# edition4-mainpart-5.net
KiCad netlist of a schematic drawn in EAGLE
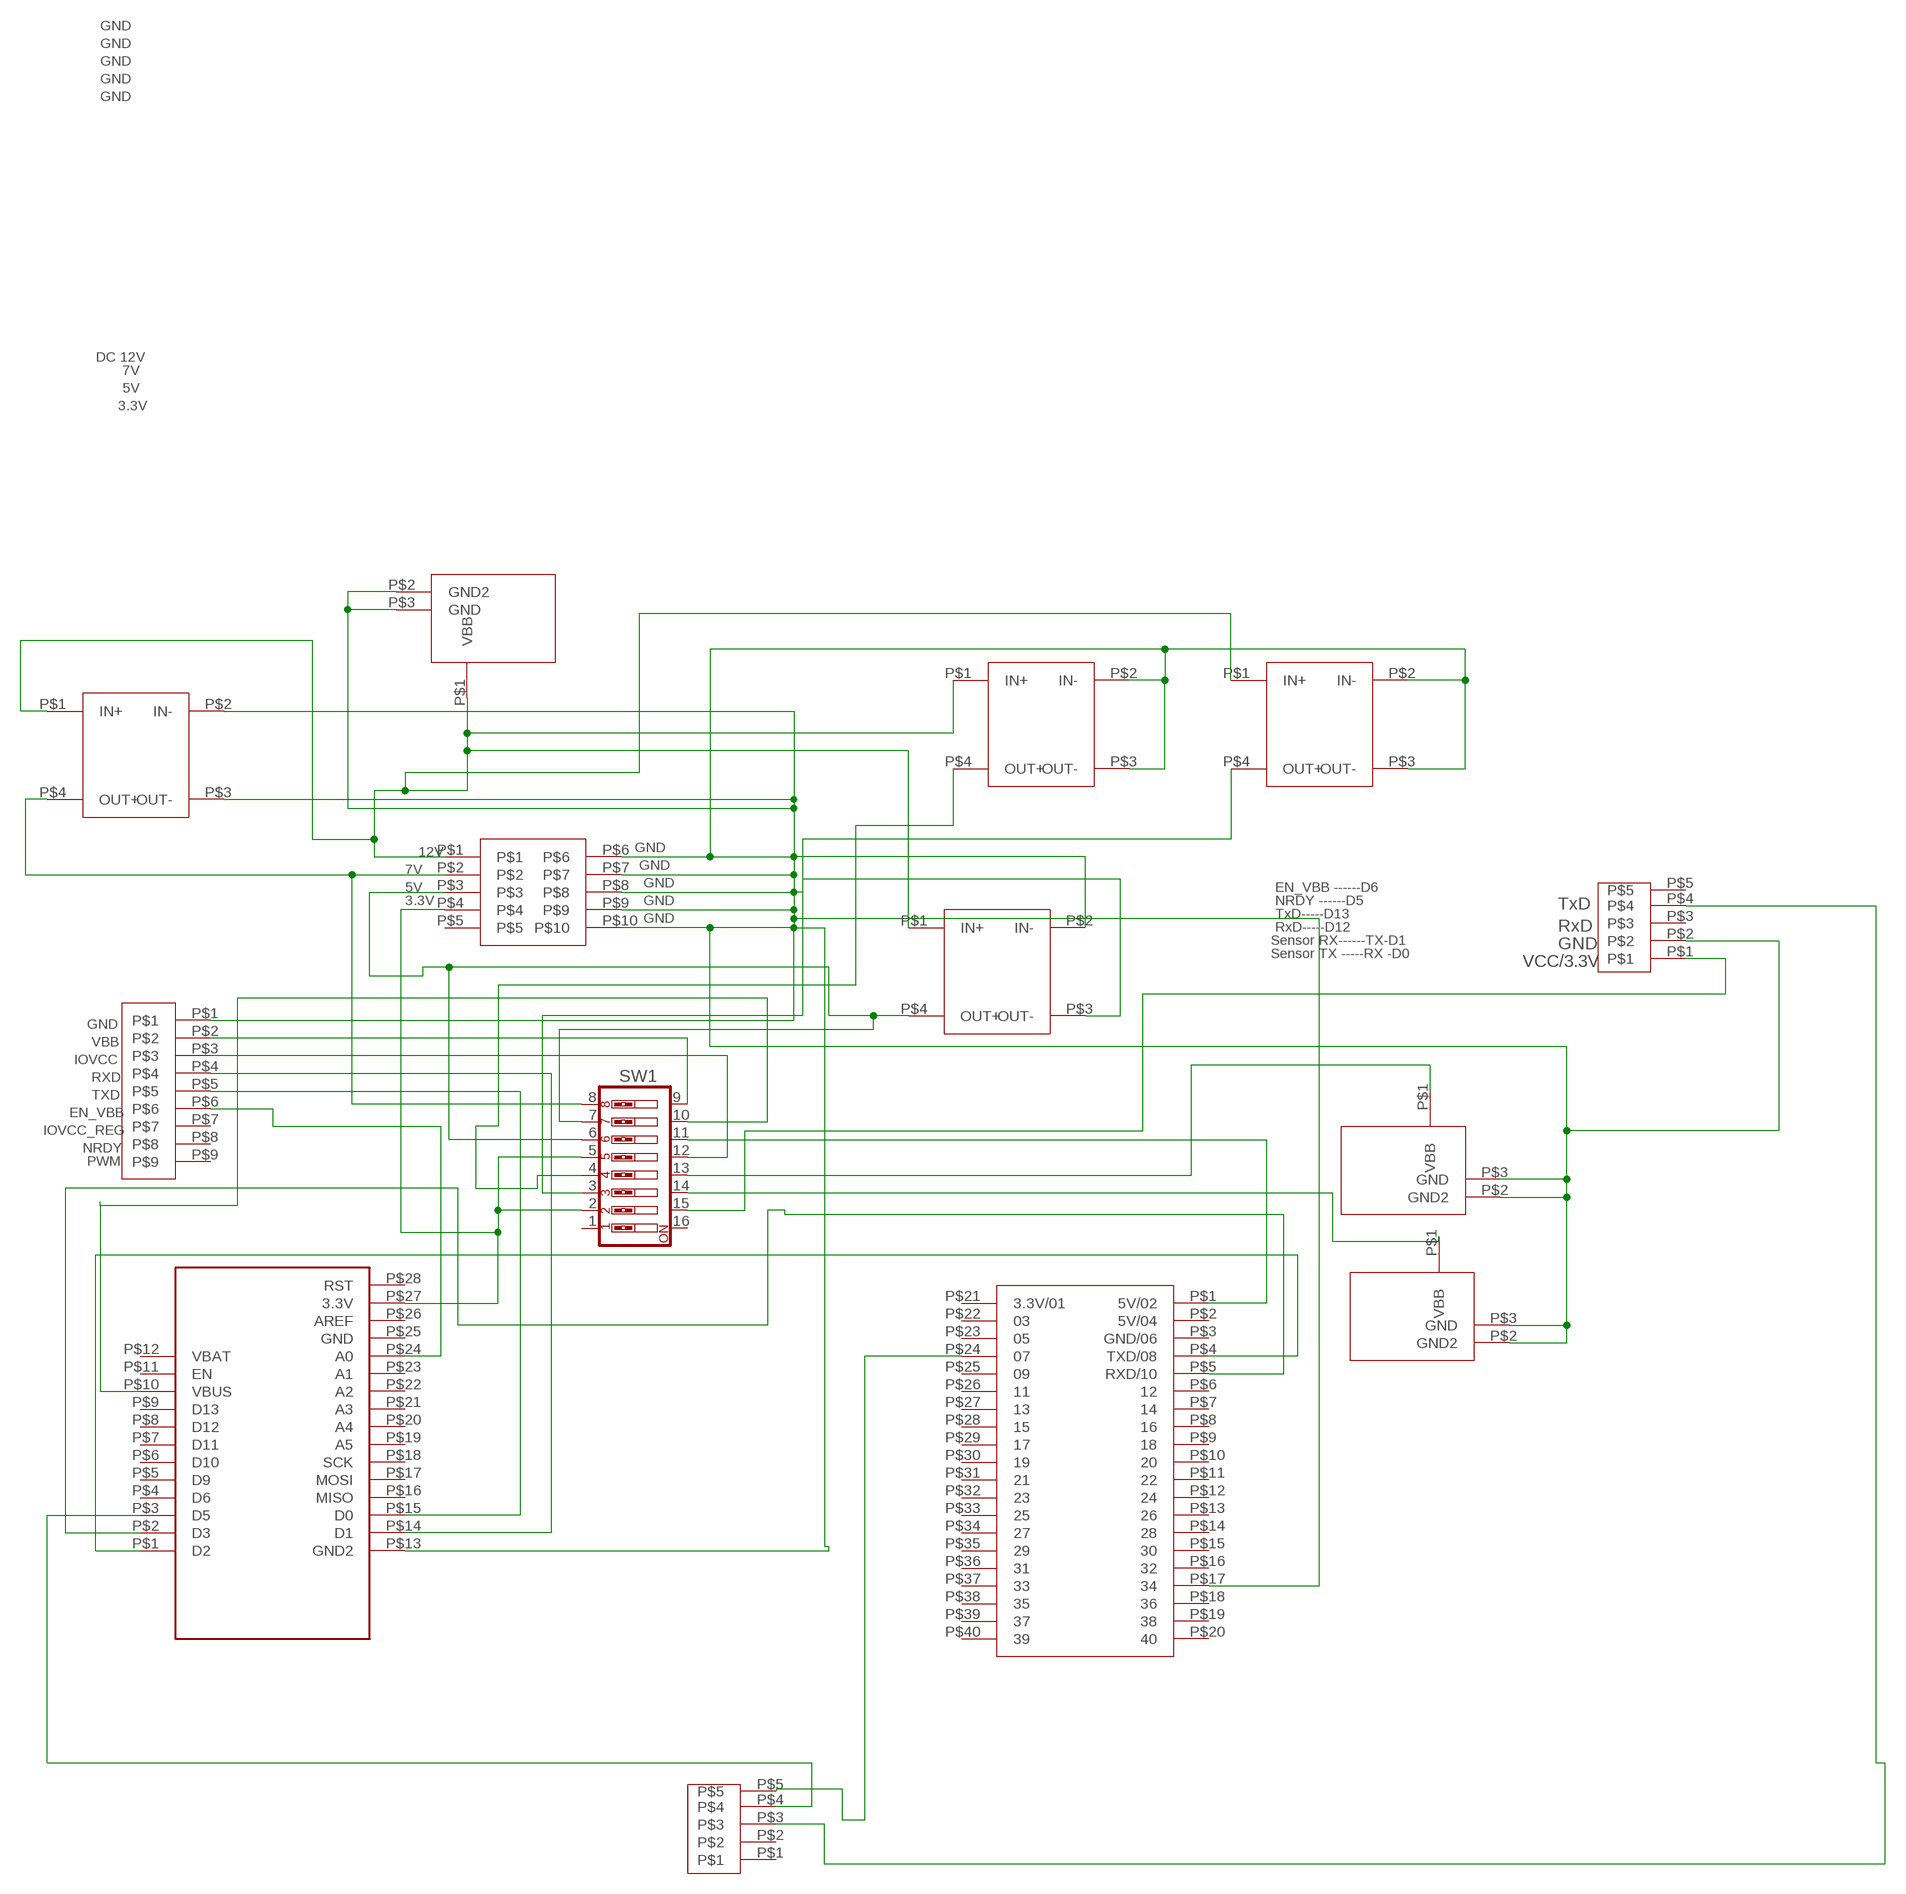
[diagram p0: schematic, sheet 1]

(export (version "E")
  (design (tool "Eeschema 10.0.6"))
  (components
    (comp (ref "SW1")
      (value "SW_DIP-8")
      (footprint "eagle-import:EDG-08")
      (libsource (lib "eagle-import") (part "SW_DIP-8"))
    )
    (comp (ref "U$1")
      (value "MH-MINI-360")
      (footprint "eagle-import:MH-MINI-360")
      (libsource (lib "eagle-import") (part "MH-MINI-360"))
    )
    (comp (ref "U$2")
      (value "MH-MINI-360")
      (footprint "eagle-import:MH-MINI-360")
      (libsource (lib "eagle-import") (part "MH-MINI-360"))
    )
    (comp (ref "U$3")
      (value "POWER")
      (footprint "eagle-import:POWERIN")
      (libsource (lib "eagle-import") (part "POWER"))
    )
    (comp (ref "U$4")
      (value "POWER")
      (footprint "eagle-import:POWERIN")
      (libsource (lib "eagle-import") (part "POWER"))
    )
    (comp (ref "U$5")
      (value "POWER")
      (footprint "eagle-import:POWERIN")
      (libsource (lib "eagle-import") (part "POWER"))
    )
    (comp (ref "U$6")
      (value "MH-MINI-360")
      (footprint "eagle-import:MH-MINI-360")
      (libsource (lib "eagle-import") (part "MH-MINI-360"))
    )
    (comp (ref "U$7")
      (value "MH-MINI-360")
      (footprint "eagle-import:MH-MINI-360")
      (libsource (lib "eagle-import") (part "MH-MINI-360"))
    )
    (comp (ref "U$8")
      (value "PIN")
      (footprint "eagle-import:PIN")
      (libsource (lib "eagle-import") (part "PIN"))
    )
    (comp (ref "U$9")
      (value "PIN")
      (footprint "eagle-import:PIN")
      (libsource (lib "eagle-import") (part "untitled (1)_PIN"))
    )
    (comp (ref "U$10")
      (value "FEATHER")
      (footprint "eagle-import:FEATHER")
      (libsource (lib "eagle-import") (part "FEATHER"))
    )
    (comp (ref "U$11")
      (value "RASPBERRYPI")
      (footprint "eagle-import:RASPBERRYPI")
      (libsource (lib "eagle-import") (part "RASPBERRYPI"))
    )
    (comp (ref "U$14")
      (value "2X5FEET")
      (footprint "eagle-import:2X5FEET")
      (libsource (lib "eagle-import") (part "2X5FEET"))
    )
    (comp (ref "U$15")
      (value "9FEETPIN")
      (footprint "eagle-import:9FEETPIN")
      (libsource (lib "eagle-import") (part "9FEETPIN"))
    )
  )
  (nets
    (net (code "1") (name "Net-(SW1-Pad9)") (class "Default")
      (node (ref "SW1") (pin "9") (pinfunction "9_9") (pintype "passive"))
      (node (ref "U$15") (pin "P$2") (pinfunction "P$2_P$2") (pintype "bidirectional"))
    )
    (net (code "2") (name "Net-(SW1-Pad12)") (class "Default")
      (node (ref "SW1") (pin "12") (pinfunction "12_12") (pintype "passive"))
      (node (ref "U$15") (pin "P$3") (pinfunction "P$3_P$3") (pintype "bidirectional"))
    )
    (net (code "3") (name "Net-(SW1-Pad15)") (class "Default")
      (node (ref "SW1") (pin "15") (pinfunction "15_15") (pintype "passive"))
      (node (ref "U$8") (pin "P$1") (pinfunction "P$1_P$1") (pintype "bidirectional"))
    )
    (net (code "4") (name "Net-(U$1-IN+)") (class "Default")
      (node (ref "U$1") (pin "P$1") (pinfunction "IN+_P$1") (pintype "bidirectional"))
      (node (ref "U$14") (pin "P$1") (pinfunction "P$1_P$1") (pintype "bidirectional"))
      (node (ref "U$2") (pin "P$1") (pinfunction "IN+_P$1") (pintype "bidirectional"))
      (node (ref "U$3") (pin "P$1") (pinfunction "VBB_P$1") (pintype "bidirectional"))
      (node (ref "U$6") (pin "P$1") (pinfunction "IN+_P$1") (pintype "bidirectional"))
      (node (ref "U$7") (pin "P$1") (pinfunction "IN+_P$1") (pintype "bidirectional"))
    )
    (net (code "5") (name "Net-(U$1-IN-)") (class "Default")
      (node (ref "U$1") (pin "P$2") (pinfunction "IN-_P$2") (pintype "bidirectional"))
      (node (ref "U$1") (pin "P$3") (pinfunction "OUT-_P$3") (pintype "bidirectional"))
      (node (ref "U$10") (pin "P$13") (pinfunction "GND2_P$13") (pintype "bidirectional"))
      (node (ref "U$11") (pin "P$17") (pinfunction "34_P$17") (pintype "bidirectional"))
      (node (ref "U$14") (pin "P$10") (pinfunction "P$10_P$10") (pintype "bidirectional"))
      (node (ref "U$14") (pin "P$6") (pinfunction "P$6_P$6") (pintype "bidirectional"))
      (node (ref "U$14") (pin "P$7") (pinfunction "P$7_P$7") (pintype "bidirectional"))
      (node (ref "U$14") (pin "P$8") (pinfunction "P$8_P$8") (pintype "bidirectional"))
      (node (ref "U$14") (pin "P$9") (pinfunction "P$9_P$9") (pintype "bidirectional"))
      (node (ref "U$15") (pin "P$1") (pinfunction "P$1_P$1") (pintype "bidirectional"))
      (node (ref "U$2") (pin "P$2") (pinfunction "IN-_P$2") (pintype "bidirectional"))
      (node (ref "U$2") (pin "P$3") (pinfunction "OUT-_P$3") (pintype "bidirectional"))
      (node (ref "U$3") (pin "P$2") (pinfunction "GND2_P$2") (pintype "bidirectional"))
      (node (ref "U$3") (pin "P$3") (pinfunction "GND_P$3") (pintype "bidirectional"))
      (node (ref "U$4") (pin "P$2") (pinfunction "GND2_P$2") (pintype "bidirectional"))
      (node (ref "U$4") (pin "P$3") (pinfunction "GND_P$3") (pintype "bidirectional"))
      (node (ref "U$5") (pin "P$2") (pinfunction "GND2_P$2") (pintype "bidirectional"))
      (node (ref "U$5") (pin "P$3") (pinfunction "GND_P$3") (pintype "bidirectional"))
      (node (ref "U$6") (pin "P$2") (pinfunction "IN-_P$2") (pintype "bidirectional"))
      (node (ref "U$6") (pin "P$3") (pinfunction "OUT-_P$3") (pintype "bidirectional"))
      (node (ref "U$7") (pin "P$2") (pinfunction "IN-_P$2") (pintype "bidirectional"))
      (node (ref "U$7") (pin "P$3") (pinfunction "OUT-_P$3") (pintype "bidirectional"))
      (node (ref "U$8") (pin "P$2") (pinfunction "P$2_P$2") (pintype "bidirectional"))
    )
    (net (code "6") (name "Net-(U$1-OUT+)") (class "Default")
      (node (ref "SW1") (pin "4") (pinfunction "4_4") (pintype "passive"))
      (node (ref "U$1") (pin "P$4") (pinfunction "OUT+_P$4") (pintype "bidirectional"))
    )
    (net (code "7") (name "Net-(U$2-OUT+)") (class "Default")
      (node (ref "SW1") (pin "6") (pinfunction "6_6") (pintype "passive"))
      (node (ref "SW1") (pin "7") (pinfunction "7_7") (pintype "passive"))
      (node (ref "U$14") (pin "P$3") (pinfunction "P$3_P$3") (pintype "bidirectional"))
      (node (ref "U$2") (pin "P$4") (pinfunction "OUT+_P$4") (pintype "bidirectional"))
    )
    (net (code "8") (name "Net-(U$4-VBB)") (class "Default")
      (node (ref "SW1") (pin "14") (pinfunction "14_14") (pintype "passive"))
      (node (ref "U$4") (pin "P$1") (pinfunction "VBB_P$1") (pintype "bidirectional"))
    )
    (net (code "9") (name "Net-(U$5-VBB)") (class "Default")
      (node (ref "SW1") (pin "13") (pinfunction "13_13") (pintype "passive"))
      (node (ref "U$5") (pin "P$1") (pinfunction "VBB_P$1") (pintype "bidirectional"))
    )
    (net (code "10") (name "Net-(U$6-OUT+)") (class "Default")
      (node (ref "SW1") (pin "8") (pinfunction "8_8") (pintype "passive"))
      (node (ref "U$14") (pin "P$2") (pinfunction "P$2_P$2") (pintype "bidirectional"))
      (node (ref "U$6") (pin "P$4") (pinfunction "OUT+_P$4") (pintype "bidirectional"))
    )
    (net (code "11") (name "Net-(U$7-OUT+)") (class "Default")
      (node (ref "SW1") (pin "3") (pinfunction "3_3") (pintype "passive"))
      (node (ref "U$7") (pin "P$4") (pinfunction "OUT+_P$4") (pintype "bidirectional"))
    )
    (net (code "12") (name "Net-(U$8-PadP$4)") (class "Default")
      (node (ref "U$8") (pin "P$4") (pinfunction "P$4_P$4") (pintype "bidirectional"))
      (node (ref "U$9") (pin "P$3") (pinfunction "P$3_P$3") (pintype "bidirectional"))
    )
    (net (code "13") (name "Net-(U$10-3.3V)") (class "Default")
      (node (ref "SW1") (pin "2") (pinfunction "2_2") (pintype "passive"))
      (node (ref "SW1") (pin "5") (pinfunction "5_5") (pintype "passive"))
      (node (ref "U$10") (pin "P$27") (pinfunction "3.3V_P$27") (pintype "bidirectional"))
      (node (ref "U$14") (pin "P$4") (pinfunction "P$4_P$4") (pintype "bidirectional"))
    )
    (net (code "14") (name "Net-(U$10-A0)") (class "Default")
      (node (ref "U$10") (pin "P$24") (pinfunction "A0_P$24") (pintype "bidirectional"))
      (node (ref "U$15") (pin "P$6") (pinfunction "P$6_P$6") (pintype "bidirectional"))
    )
    (net (code "15") (name "Net-(U$10-D0)") (class "Default")
      (node (ref "U$10") (pin "P$15") (pinfunction "D0_P$15") (pintype "bidirectional"))
      (node (ref "U$15") (pin "P$5") (pinfunction "P$5_P$5") (pintype "bidirectional"))
    )
    (net (code "16") (name "Net-(U$10-D1)") (class "Default")
      (node (ref "U$10") (pin "P$14") (pinfunction "D1_P$14") (pintype "bidirectional"))
      (node (ref "U$15") (pin "P$4") (pinfunction "P$4_P$4") (pintype "bidirectional"))
    )
    (net (code "17") (name "Net-(U$10-D2)") (class "Default")
      (node (ref "U$10") (pin "P$1") (pinfunction "D2_P$1") (pintype "bidirectional"))
      (node (ref "U$11") (pin "P$4") (pinfunction "TXD/08_P$4") (pintype "bidirectional"))
    )
    (net (code "18") (name "Net-(U$10-D3)") (class "Default")
      (node (ref "U$10") (pin "P$2") (pinfunction "D3_P$2") (pintype "bidirectional"))
      (node (ref "U$11") (pin "P$5") (pinfunction "RXD/10_P$5") (pintype "bidirectional"))
    )
    (net (code "19") (name "Net-(U$10-D5)") (class "Default")
      (node (ref "U$10") (pin "P$3") (pinfunction "D5_P$3") (pintype "bidirectional"))
      (node (ref "U$9") (pin "P$4") (pinfunction "P$4_P$4") (pintype "bidirectional"))
    )
    (net (code "20") (name "Net-(U$10-VBUS)") (class "Default")
      (node (ref "SW1") (pin "10") (pinfunction "10_10") (pintype "passive"))
      (node (ref "U$10") (pin "P$10") (pinfunction "VBUS_P$10") (pintype "bidirectional"))
    )
    (net (code "21") (name "Net-(U$11-5V{slash}02)") (class "Default")
      (node (ref "SW1") (pin "11") (pinfunction "11_11") (pintype "passive"))
      (node (ref "U$11") (pin "P$1") (pinfunction "5V/02_P$1") (pintype "bidirectional"))
    )
    (net (code "22") (name "Net-(U$11-07)") (class "Default")
      (node (ref "U$11") (pin "P$24") (pinfunction "07_P$24") (pintype "bidirectional"))
      (node (ref "U$9") (pin "P$5") (pinfunction "P$5_P$5") (pintype "bidirectional"))
    )
    (net (code "23") (name "unconnected-(SW1-Pad1)") (class "Default")
      (node (ref "SW1") (pin "1") (pinfunction "1_1") (pintype "passive"))
    )
    (net (code "24") (name "unconnected-(SW1-Pad16)") (class "Default")
      (node (ref "SW1") (pin "16") (pinfunction "16_16") (pintype "passive"))
    )
    (net (code "25") (name "unconnected-(U$8-PadP$3)") (class "Default")
      (node (ref "U$8") (pin "P$3") (pinfunction "P$3_P$3") (pintype "bidirectional"))
    )
    (net (code "26") (name "unconnected-(U$8-PadP$5)") (class "Default")
      (node (ref "U$8") (pin "P$5") (pinfunction "P$5_P$5") (pintype "bidirectional"))
    )
    (net (code "27") (name "unconnected-(U$9-PadP$1)") (class "Default")
      (node (ref "U$9") (pin "P$1") (pinfunction "P$1_P$1") (pintype "bidirectional"))
    )
    (net (code "28") (name "unconnected-(U$9-PadP$2)") (class "Default")
      (node (ref "U$9") (pin "P$2") (pinfunction "P$2_P$2") (pintype "bidirectional"))
    )
    (net (code "29") (name "unconnected-(U$10-A1-PadP$23)") (class "Default")
      (node (ref "U$10") (pin "P$23") (pinfunction "A1_P$23") (pintype "bidirectional"))
    )
    (net (code "30") (name "unconnected-(U$10-A2-PadP$22)") (class "Default")
      (node (ref "U$10") (pin "P$22") (pinfunction "A2_P$22") (pintype "bidirectional"))
    )
    (net (code "31") (name "unconnected-(U$10-A3-PadP$21)") (class "Default")
      (node (ref "U$10") (pin "P$21") (pinfunction "A3_P$21") (pintype "bidirectional"))
    )
    (net (code "32") (name "unconnected-(U$10-A4-PadP$20)") (class "Default")
      (node (ref "U$10") (pin "P$20") (pinfunction "A4_P$20") (pintype "bidirectional"))
    )
    (net (code "33") (name "unconnected-(U$10-A5-PadP$19)") (class "Default")
      (node (ref "U$10") (pin "P$19") (pinfunction "A5_P$19") (pintype "bidirectional"))
    )
    (net (code "34") (name "unconnected-(U$10-AREF-PadP$26)") (class "Default")
      (node (ref "U$10") (pin "P$26") (pinfunction "AREF_P$26") (pintype "bidirectional"))
    )
    (net (code "35") (name "unconnected-(U$10-D6-PadP$4)") (class "Default")
      (node (ref "U$10") (pin "P$4") (pinfunction "D6_P$4") (pintype "bidirectional"))
    )
    (net (code "36") (name "unconnected-(U$10-D9-PadP$5)") (class "Default")
      (node (ref "U$10") (pin "P$5") (pinfunction "D9_P$5") (pintype "bidirectional"))
    )
    (net (code "37") (name "unconnected-(U$10-D10-PadP$6)") (class "Default")
      (node (ref "U$10") (pin "P$6") (pinfunction "D10_P$6") (pintype "bidirectional"))
    )
    (net (code "38") (name "unconnected-(U$10-D11-PadP$7)") (class "Default")
      (node (ref "U$10") (pin "P$7") (pinfunction "D11_P$7") (pintype "bidirectional"))
    )
    (net (code "39") (name "unconnected-(U$10-D12-PadP$8)") (class "Default")
      (node (ref "U$10") (pin "P$8") (pinfunction "D12_P$8") (pintype "bidirectional"))
    )
    (net (code "40") (name "unconnected-(U$10-D13-PadP$9)") (class "Default")
      (node (ref "U$10") (pin "P$9") (pinfunction "D13_P$9") (pintype "bidirectional"))
    )
    (net (code "41") (name "unconnected-(U$10-EN-PadP$11)") (class "Default")
      (node (ref "U$10") (pin "P$11") (pinfunction "EN_P$11") (pintype "bidirectional"))
    )
    (net (code "42") (name "unconnected-(U$10-GND-PadP$25)") (class "Default")
      (node (ref "U$10") (pin "P$25") (pinfunction "GND_P$25") (pintype "bidirectional"))
    )
    (net (code "43") (name "unconnected-(U$10-MISO-PadP$16)") (class "Default")
      (node (ref "U$10") (pin "P$16") (pinfunction "MISO_P$16") (pintype "bidirectional"))
    )
    (net (code "44") (name "unconnected-(U$10-MOSI-PadP$17)") (class "Default")
      (node (ref "U$10") (pin "P$17") (pinfunction "MOSI_P$17") (pintype "bidirectional"))
    )
    (net (code "45") (name "unconnected-(U$10-RST-PadP$28)") (class "Default")
      (node (ref "U$10") (pin "P$28") (pinfunction "RST_P$28") (pintype "bidirectional"))
    )
    (net (code "46") (name "unconnected-(U$10-SCK-PadP$18)") (class "Default")
      (node (ref "U$10") (pin "P$18") (pinfunction "SCK_P$18") (pintype "bidirectional"))
    )
    (net (code "47") (name "unconnected-(U$10-VBAT-PadP$12)") (class "Default")
      (node (ref "U$10") (pin "P$12") (pinfunction "VBAT_P$12") (pintype "bidirectional"))
    )
    (net (code "48") (name "unconnected-(U$11-03-PadP$22)") (class "Default")
      (node (ref "U$11") (pin "P$22") (pinfunction "03_P$22") (pintype "bidirectional"))
    )
    (net (code "49") (name "unconnected-(U$11-3.3V{slash}01-PadP$21)") (class "Default")
      (node (ref "U$11") (pin "P$21") (pinfunction "3.3V/01_P$21") (pintype "bidirectional"))
    )
    (net (code "50") (name "unconnected-(U$11-05-PadP$23)") (class "Default")
      (node (ref "U$11") (pin "P$23") (pinfunction "05_P$23") (pintype "bidirectional"))
    )
    (net (code "51") (name "unconnected-(U$11-5V{slash}04-PadP$2)") (class "Default")
      (node (ref "U$11") (pin "P$2") (pinfunction "5V/04_P$2") (pintype "bidirectional"))
    )
    (net (code "52") (name "unconnected-(U$11-09-PadP$25)") (class "Default")
      (node (ref "U$11") (pin "P$25") (pinfunction "09_P$25") (pintype "bidirectional"))
    )
    (net (code "53") (name "unconnected-(U$11-11-PadP$26)") (class "Default")
      (node (ref "U$11") (pin "P$26") (pinfunction "11_P$26") (pintype "bidirectional"))
    )
    (net (code "54") (name "unconnected-(U$11-12-PadP$6)") (class "Default")
      (node (ref "U$11") (pin "P$6") (pinfunction "12_P$6") (pintype "bidirectional"))
    )
    (net (code "55") (name "unconnected-(U$11-13-PadP$27)") (class "Default")
      (node (ref "U$11") (pin "P$27") (pinfunction "13_P$27") (pintype "bidirectional"))
    )
    (net (code "56") (name "unconnected-(U$11-14-PadP$7)") (class "Default")
      (node (ref "U$11") (pin "P$7") (pinfunction "14_P$7") (pintype "bidirectional"))
    )
    (net (code "57") (name "unconnected-(U$11-15-PadP$28)") (class "Default")
      (node (ref "U$11") (pin "P$28") (pinfunction "15_P$28") (pintype "bidirectional"))
    )
    (net (code "58") (name "unconnected-(U$11-16-PadP$8)") (class "Default")
      (node (ref "U$11") (pin "P$8") (pinfunction "16_P$8") (pintype "bidirectional"))
    )
    (net (code "59") (name "unconnected-(U$11-17-PadP$29)") (class "Default")
      (node (ref "U$11") (pin "P$29") (pinfunction "17_P$29") (pintype "bidirectional"))
    )
    (net (code "60") (name "unconnected-(U$11-18-PadP$9)") (class "Default")
      (node (ref "U$11") (pin "P$9") (pinfunction "18_P$9") (pintype "bidirectional"))
    )
    (net (code "61") (name "unconnected-(U$11-19-PadP$30)") (class "Default")
      (node (ref "U$11") (pin "P$30") (pinfunction "19_P$30") (pintype "bidirectional"))
    )
    (net (code "62") (name "unconnected-(U$11-20-PadP$10)") (class "Default")
      (node (ref "U$11") (pin "P$10") (pinfunction "20_P$10") (pintype "bidirectional"))
    )
    (net (code "63") (name "unconnected-(U$11-21-PadP$31)") (class "Default")
      (node (ref "U$11") (pin "P$31") (pinfunction "21_P$31") (pintype "bidirectional"))
    )
    (net (code "64") (name "unconnected-(U$11-22-PadP$11)") (class "Default")
      (node (ref "U$11") (pin "P$11") (pinfunction "22_P$11") (pintype "bidirectional"))
    )
    (net (code "65") (name "unconnected-(U$11-23-PadP$32)") (class "Default")
      (node (ref "U$11") (pin "P$32") (pinfunction "23_P$32") (pintype "bidirectional"))
    )
    (net (code "66") (name "unconnected-(U$11-24-PadP$12)") (class "Default")
      (node (ref "U$11") (pin "P$12") (pinfunction "24_P$12") (pintype "bidirectional"))
    )
    (net (code "67") (name "unconnected-(U$11-25-PadP$33)") (class "Default")
      (node (ref "U$11") (pin "P$33") (pinfunction "25_P$33") (pintype "bidirectional"))
    )
    (net (code "68") (name "unconnected-(U$11-26-PadP$13)") (class "Default")
      (node (ref "U$11") (pin "P$13") (pinfunction "26_P$13") (pintype "bidirectional"))
    )
    (net (code "69") (name "unconnected-(U$11-27-PadP$34)") (class "Default")
      (node (ref "U$11") (pin "P$34") (pinfunction "27_P$34") (pintype "bidirectional"))
    )
    (net (code "70") (name "unconnected-(U$11-28-PadP$14)") (class "Default")
      (node (ref "U$11") (pin "P$14") (pinfunction "28_P$14") (pintype "bidirectional"))
    )
    (net (code "71") (name "unconnected-(U$11-29-PadP$35)") (class "Default")
      (node (ref "U$11") (pin "P$35") (pinfunction "29_P$35") (pintype "bidirectional"))
    )
    (net (code "72") (name "unconnected-(U$11-30-PadP$15)") (class "Default")
      (node (ref "U$11") (pin "P$15") (pinfunction "30_P$15") (pintype "bidirectional"))
    )
    (net (code "73") (name "unconnected-(U$11-31-PadP$36)") (class "Default")
      (node (ref "U$11") (pin "P$36") (pinfunction "31_P$36") (pintype "bidirectional"))
    )
    (net (code "74") (name "unconnected-(U$11-32-PadP$16)") (class "Default")
      (node (ref "U$11") (pin "P$16") (pinfunction "32_P$16") (pintype "bidirectional"))
    )
    (net (code "75") (name "unconnected-(U$11-33-PadP$37)") (class "Default")
      (node (ref "U$11") (pin "P$37") (pinfunction "33_P$37") (pintype "bidirectional"))
    )
    (net (code "76") (name "unconnected-(U$11-35-PadP$38)") (class "Default")
      (node (ref "U$11") (pin "P$38") (pinfunction "35_P$38") (pintype "bidirectional"))
    )
    (net (code "77") (name "unconnected-(U$11-36-PadP$18)") (class "Default")
      (node (ref "U$11") (pin "P$18") (pinfunction "36_P$18") (pintype "bidirectional"))
    )
    (net (code "78") (name "unconnected-(U$11-37-PadP$39)") (class "Default")
      (node (ref "U$11") (pin "P$39") (pinfunction "37_P$39") (pintype "bidirectional"))
    )
    (net (code "79") (name "unconnected-(U$11-38-PadP$19)") (class "Default")
      (node (ref "U$11") (pin "P$19") (pinfunction "38_P$19") (pintype "bidirectional"))
    )
    (net (code "80") (name "unconnected-(U$11-39-PadP$40)") (class "Default")
      (node (ref "U$11") (pin "P$40") (pinfunction "39_P$40") (pintype "bidirectional"))
    )
    (net (code "81") (name "unconnected-(U$11-40-PadP$20)") (class "Default")
      (node (ref "U$11") (pin "P$20") (pinfunction "40_P$20") (pintype "bidirectional"))
    )
    (net (code "82") (name "unconnected-(U$11-GND{slash}06-PadP$3)") (class "Default")
      (node (ref "U$11") (pin "P$3") (pinfunction "GND/06_P$3") (pintype "bidirectional"))
    )
    (net (code "83") (name "unconnected-(U$14-PadP$5)") (class "Default")
      (node (ref "U$14") (pin "P$5") (pinfunction "P$5_P$5") (pintype "bidirectional"))
    )
    (net (code "84") (name "unconnected-(U$15-PadP$7)") (class "Default")
      (node (ref "U$15") (pin "P$7") (pinfunction "P$7_P$7") (pintype "bidirectional"))
    )
    (net (code "85") (name "unconnected-(U$15-PadP$8)") (class "Default")
      (node (ref "U$15") (pin "P$8") (pinfunction "P$8_P$8") (pintype "bidirectional"))
    )
    (net (code "86") (name "unconnected-(U$15-PadP$9)") (class "Default")
      (node (ref "U$15") (pin "P$9") (pinfunction "P$9_P$9") (pintype "bidirectional"))
    )
  )
)
